# 01_USB_Interface.net
KiCad netlist of a schematic drawn in Altium Designer
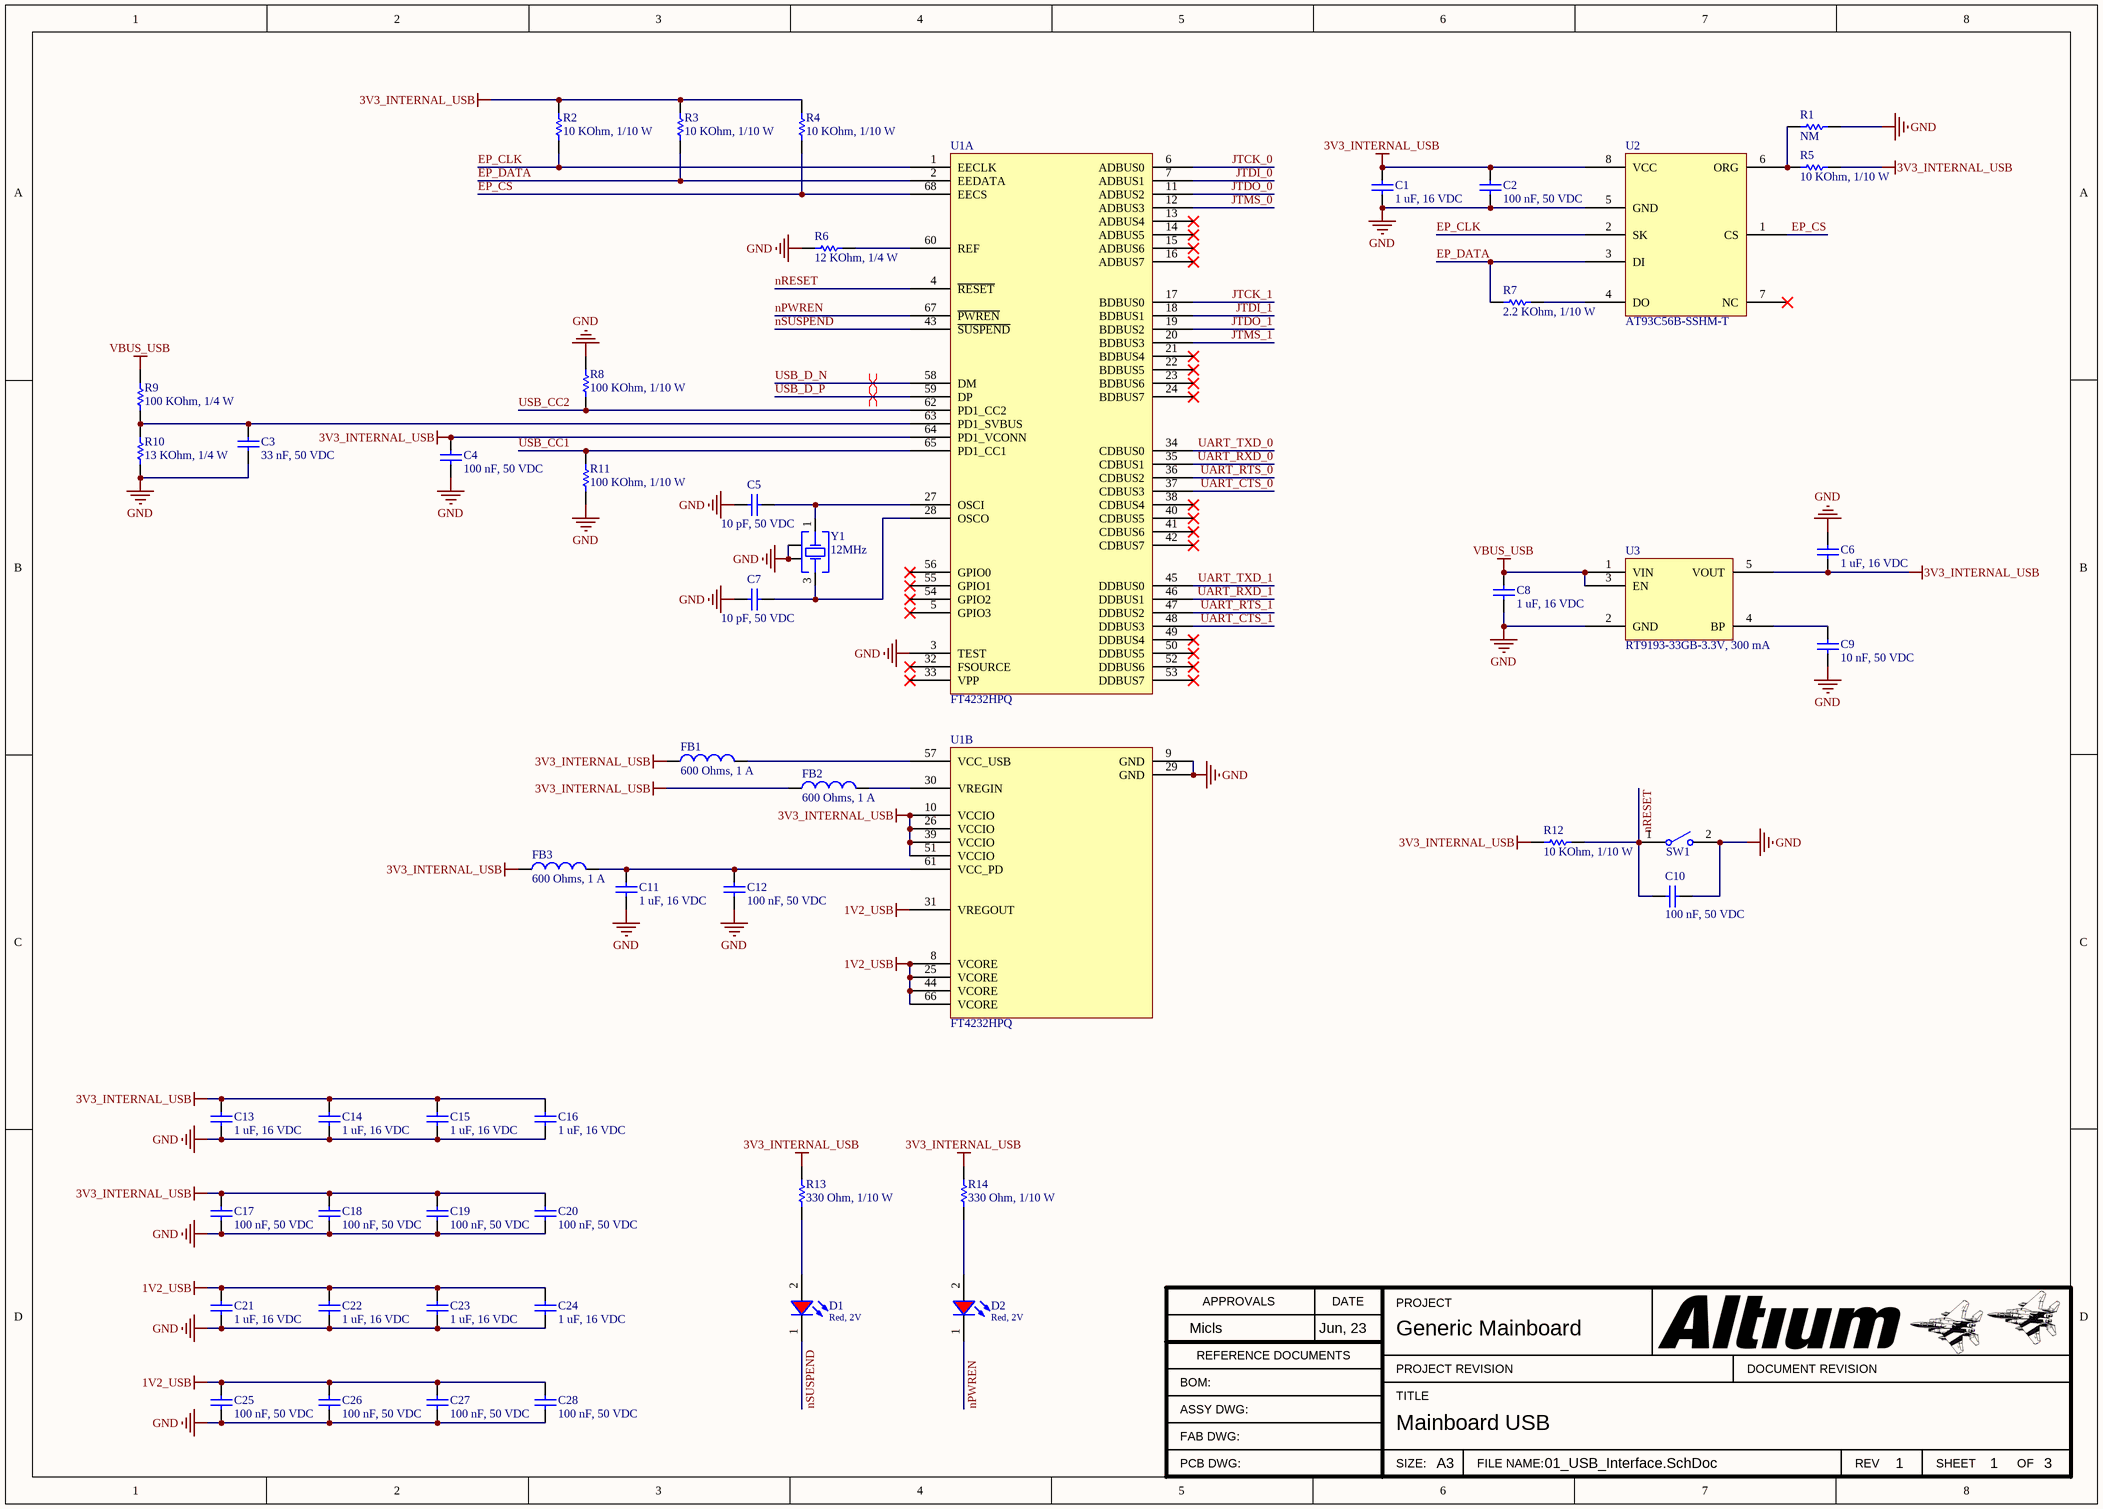
[diagram p0: 01_USB_Interface.SchDoc]

(export (version "E")
  (design (tool "Eeschema 10.0.6"))
  (components
    (comp (ref "C1")
      (value "1 uF, 16 VDC")
      (footprint "CAP_0603")
      (description "CAP, size 0603, 1 uF, 16 VDC")
      (fields (field (name "TOLERANCE") "+/-10%") (field (name "MANUFACTURER") "Samsung Electro-Mechanics"))
      (libsource (lib "Altium_Ceramic_Cap") (part "0106031051016"))
    )
    (comp (ref "C2")
      (value "100 nF, 50 VDC")
      (footprint "CAP_0603")
      (description "CAP, size 0603, 100 nF, 50 VDC")
      (fields (field (name "TOLERANCE") "+/-10%") (field (name "MANUFACTURER") "TDK"))
      (libsource (lib "Altium_Ceramic_Cap") (part "0106031041050"))
    )
    (comp (ref "C3")
      (value "33 nF, 50 VDC")
      (footprint "CAP_0603")
      (description "CAP, size 0603, 33 nF, 50 VDC")
      (fields (field (name "TOLERANCE") "+/-10%") (field (name "MANUFACTURER") "TDK"))
      (libsource (lib "Altium_Ceramic_Cap") (part "0106033331050"))
    )
    (comp (ref "C4")
      (value "100 nF, 50 VDC")
      (footprint "CAP_0603")
      (description "CAP, size 0603, 100 nF, 50 VDC")
      (fields (field (name "TOLERANCE") "+/-10%") (field (name "MANUFACTURER") "TDK"))
      (libsource (lib "Altium_Ceramic_Cap") (part "0106031041050"))
    )
    (comp (ref "C5")
      (value "10 pF, 50 VDC")
      (footprint "CAP_0603")
      (description "CAP, size 0603, 10 pF, 50 VDC")
      (fields (field (name "TOLERANCE") "+/-5%") (field (name "MANUFACTURER") "TDK"))
      (libsource (lib "Altium_Ceramic_Cap") (part "0106031000550"))
    )
    (comp (ref "C6")
      (value "1 uF, 16 VDC")
      (footprint "CAP_0603")
      (description "CAP, size 0603, 1 uF, 16 VDC")
      (fields (field (name "TOLERANCE") "+/-10%") (field (name "MANUFACTURER") "Samsung Electro-Mechanics"))
      (libsource (lib "Altium_Ceramic_Cap") (part "0106031051016"))
    )
    (comp (ref "C7")
      (value "10 pF, 50 VDC")
      (footprint "CAP_0603")
      (description "CAP, size 0603, 10 pF, 50 VDC")
      (fields (field (name "TOLERANCE") "+/-5%") (field (name "MANUFACTURER") "TDK"))
      (libsource (lib "Altium_Ceramic_Cap") (part "0106031000550"))
    )
    (comp (ref "C8")
      (value "1 uF, 16 VDC")
      (footprint "CAP_0603")
      (description "CAP, size 0603, 1 uF, 16 VDC")
      (fields (field (name "TOLERANCE") "+/-10%") (field (name "MANUFACTURER") "Samsung Electro-Mechanics"))
      (libsource (lib "Altium_Ceramic_Cap") (part "0106031051016"))
    )
    (comp (ref "C9")
      (value "10 nF, 50 VDC")
      (footprint "CAP_0603")
      (description "CAP, size 0603, 10 nF, 50 VDC")
      (fields (field (name "TOLERANCE") "+/-5%") (field (name "MANUFACTURER") "TDK"))
      (libsource (lib "Altium_Ceramic_Cap") (part "0106031030550"))
    )
    (comp (ref "C10")
      (value "100 nF, 50 VDC")
      (footprint "CAP_0603")
      (description "CAP, size 0603, 100 nF, 50 VDC")
      (fields (field (name "TOLERANCE") "+/-10%") (field (name "MANUFACTURER") "TDK"))
      (libsource (lib "Altium_Ceramic_Cap") (part "0106031041050"))
    )
    (comp (ref "C11")
      (value "1 uF, 16 VDC")
      (footprint "CAP_0603")
      (description "CAP, size 0603, 1 uF, 16 VDC")
      (fields (field (name "TOLERANCE") "+/-10%") (field (name "MANUFACTURER") "Samsung Electro-Mechanics"))
      (libsource (lib "Altium_Ceramic_Cap") (part "0106031051016"))
    )
    (comp (ref "C12")
      (value "100 nF, 50 VDC")
      (footprint "CAP_0603")
      (description "CAP, size 0603, 100 nF, 50 VDC")
      (fields (field (name "TOLERANCE") "+/-10%") (field (name "MANUFACTURER") "TDK"))
      (libsource (lib "Altium_Ceramic_Cap") (part "0106031041050"))
    )
    (comp (ref "C13")
      (value "1 uF, 16 VDC")
      (footprint "CAP_0603")
      (description "CAP, size 0603, 1 uF, 16 VDC")
      (fields (field (name "TOLERANCE") "+/-10%") (field (name "MANUFACTURER") "Samsung Electro-Mechanics"))
      (libsource (lib "Altium_Ceramic_Cap") (part "0106031051016"))
    )
    (comp (ref "C14")
      (value "1 uF, 16 VDC")
      (footprint "CAP_0603")
      (description "CAP, size 0603, 1 uF, 16 VDC")
      (fields (field (name "TOLERANCE") "+/-10%") (field (name "MANUFACTURER") "Samsung Electro-Mechanics"))
      (libsource (lib "Altium_Ceramic_Cap") (part "0106031051016"))
    )
    (comp (ref "C15")
      (value "1 uF, 16 VDC")
      (footprint "CAP_0603")
      (description "CAP, size 0603, 1 uF, 16 VDC")
      (fields (field (name "TOLERANCE") "+/-10%") (field (name "MANUFACTURER") "Samsung Electro-Mechanics"))
      (libsource (lib "Altium_Ceramic_Cap") (part "0106031051016"))
    )
    (comp (ref "C16")
      (value "1 uF, 16 VDC")
      (footprint "CAP_0603")
      (description "CAP, size 0603, 1 uF, 16 VDC")
      (fields (field (name "TOLERANCE") "+/-10%") (field (name "MANUFACTURER") "Samsung Electro-Mechanics"))
      (libsource (lib "Altium_Ceramic_Cap") (part "0106031051016"))
    )
    (comp (ref "C17")
      (value "100 nF, 50 VDC")
      (footprint "CAP_0603")
      (description "CAP, size 0603, 100 nF, 50 VDC")
      (fields (field (name "TOLERANCE") "+/-10%") (field (name "MANUFACTURER") "TDK"))
      (libsource (lib "Altium_Ceramic_Cap") (part "0106031041050"))
    )
    (comp (ref "C18")
      (value "100 nF, 50 VDC")
      (footprint "CAP_0603")
      (description "CAP, size 0603, 100 nF, 50 VDC")
      (fields (field (name "TOLERANCE") "+/-10%") (field (name "MANUFACTURER") "TDK"))
      (libsource (lib "Altium_Ceramic_Cap") (part "0106031041050"))
    )
    (comp (ref "C19")
      (value "100 nF, 50 VDC")
      (footprint "CAP_0603")
      (description "CAP, size 0603, 100 nF, 50 VDC")
      (fields (field (name "TOLERANCE") "+/-10%") (field (name "MANUFACTURER") "TDK"))
      (libsource (lib "Altium_Ceramic_Cap") (part "0106031041050"))
    )
    (comp (ref "C20")
      (value "100 nF, 50 VDC")
      (footprint "CAP_0603")
      (description "CAP, size 0603, 100 nF, 50 VDC")
      (fields (field (name "TOLERANCE") "+/-10%") (field (name "MANUFACTURER") "TDK"))
      (libsource (lib "Altium_Ceramic_Cap") (part "0106031041050"))
    )
    (comp (ref "C21")
      (value "1 uF, 16 VDC")
      (footprint "CAP_0603")
      (description "CAP, size 0603, 1 uF, 16 VDC")
      (fields (field (name "TOLERANCE") "+/-10%") (field (name "MANUFACTURER") "Samsung Electro-Mechanics"))
      (libsource (lib "Altium_Ceramic_Cap") (part "0106031051016"))
    )
    (comp (ref "C22")
      (value "1 uF, 16 VDC")
      (footprint "CAP_0603")
      (description "CAP, size 0603, 1 uF, 16 VDC")
      (fields (field (name "TOLERANCE") "+/-10%") (field (name "MANUFACTURER") "Samsung Electro-Mechanics"))
      (libsource (lib "Altium_Ceramic_Cap") (part "0106031051016"))
    )
    (comp (ref "C23")
      (value "1 uF, 16 VDC")
      (footprint "CAP_0603")
      (description "CAP, size 0603, 1 uF, 16 VDC")
      (fields (field (name "TOLERANCE") "+/-10%") (field (name "MANUFACTURER") "Samsung Electro-Mechanics"))
      (libsource (lib "Altium_Ceramic_Cap") (part "0106031051016"))
    )
    (comp (ref "C24")
      (value "1 uF, 16 VDC")
      (footprint "CAP_0603")
      (description "CAP, size 0603, 1 uF, 16 VDC")
      (fields (field (name "TOLERANCE") "+/-10%") (field (name "MANUFACTURER") "Samsung Electro-Mechanics"))
      (libsource (lib "Altium_Ceramic_Cap") (part "0106031051016"))
    )
    (comp (ref "C25")
      (value "100 nF, 50 VDC")
      (footprint "CAP_0603")
      (description "CAP, size 0603, 100 nF, 50 VDC")
      (fields (field (name "TOLERANCE") "+/-10%") (field (name "MANUFACTURER") "TDK"))
      (libsource (lib "Altium_Ceramic_Cap") (part "0106031041050"))
    )
    (comp (ref "C26")
      (value "100 nF, 50 VDC")
      (footprint "CAP_0603")
      (description "CAP, size 0603, 100 nF, 50 VDC")
      (fields (field (name "TOLERANCE") "+/-10%") (field (name "MANUFACTURER") "TDK"))
      (libsource (lib "Altium_Ceramic_Cap") (part "0106031041050"))
    )
    (comp (ref "C27")
      (value "100 nF, 50 VDC")
      (footprint "CAP_0603")
      (description "CAP, size 0603, 100 nF, 50 VDC")
      (fields (field (name "TOLERANCE") "+/-10%") (field (name "MANUFACTURER") "TDK"))
      (libsource (lib "Altium_Ceramic_Cap") (part "0106031041050"))
    )
    (comp (ref "C28")
      (value "100 nF, 50 VDC")
      (footprint "CAP_0603")
      (description "CAP, size 0603, 100 nF, 50 VDC")
      (fields (field (name "TOLERANCE") "+/-10%") (field (name "MANUFACTURER") "TDK"))
      (libsource (lib "Altium_Ceramic_Cap") (part "0106031041050"))
    )
    (comp (ref "D1")
      (value "Red, 2V")
      (footprint "WL-SMCW_0603_H=0.7mm")
      (description "WL-SMCW SMT Mono-color Chip LED Blur, size 0603, Red, 2V, 140deg")
      (fields
        (field (name "MANUFACTURER") "ROHM Semiconductor")
        (field (name "MANUFACTURER PART NUMBER") "CSL1901VW1")
      )
      (libsource (lib "Altium_LED") (part "160603RedBlur"))
    )
    (comp (ref "D2")
      (value "Red, 2V")
      (footprint "WL-SMCW_0603_H=0.7mm")
      (description "WL-SMCW SMT Mono-color Chip LED Blur, size 0603, Red, 2V, 140deg")
      (fields
        (field (name "MANUFACTURER") "ROHM Semiconductor")
        (field (name "MANUFACTURER PART NUMBER") "CSL1901VW1")
      )
      (libsource (lib "Altium_LED") (part "160603RedBlur"))
    )
    (comp (ref "FB1")
      (value "600 Ohms, 1 A")
      (footprint "FER_0603")
      (description "Ferrite, 0603, 600 Ohms, 1 A")
      (fields (field (name "TOLERANCE") "+/-25%") (field (name "MANUFACTURER") "Wurth Elektronik"))
      (libsource (lib "Altium_Ferrite_Bead") (part "03060360110225"))
    )
    (comp (ref "FB2")
      (value "600 Ohms, 1 A")
      (footprint "FER_0603")
      (description "Ferrite, 0603, 600 Ohms, 1 A")
      (fields (field (name "TOLERANCE") "+/-25%") (field (name "MANUFACTURER") "Wurth Elektronik"))
      (libsource (lib "Altium_Ferrite_Bead") (part "03060360110225"))
    )
    (comp (ref "FB3")
      (value "600 Ohms, 1 A")
      (footprint "FER_0603")
      (description "Ferrite, 0603, 600 Ohms, 1 A")
      (fields (field (name "TOLERANCE") "+/-25%") (field (name "MANUFACTURER") "Wurth Elektronik"))
      (libsource (lib "Altium_Ferrite_Bead") (part "03060360110225"))
    )
    (comp (ref "R1")
      (value "NM")
      (footprint "RES_0603")
      (description "RES, size 0603, NM, N/A")
      (libsource (lib "Altium_Resistor") (part "000603_NM"))
    )
    (comp (ref "R2")
      (value "10 KOhm, 1/10 W")
      (footprint "RES_0603")
      (description "RES, size 0603, 10 KOhm, 1/10 W, 1%")
      (fields (field (name "TOLERANCE") "+/-1%") (field (name "MANUFACTURER") "YAGEO"))
      (libsource (lib "Altium_Resistor") (part "0006031031"))
    )
    (comp (ref "R3")
      (value "10 KOhm, 1/10 W")
      (footprint "RES_0603")
      (description "RES, size 0603, 10 KOhm, 1/10 W, 1%")
      (fields (field (name "TOLERANCE") "+/-1%") (field (name "MANUFACTURER") "YAGEO"))
      (libsource (lib "Altium_Resistor") (part "0006031031"))
    )
    (comp (ref "R4")
      (value "10 KOhm, 1/10 W")
      (footprint "RES_0603")
      (description "RES, size 0603, 10 KOhm, 1/10 W, 1%")
      (fields (field (name "TOLERANCE") "+/-1%") (field (name "MANUFACTURER") "YAGEO"))
      (libsource (lib "Altium_Resistor") (part "0006031031"))
    )
    (comp (ref "R5")
      (value "10 KOhm, 1/10 W")
      (footprint "RES_0603")
      (description "RES, size 0603, 10 KOhm, 1/10 W, 1%")
      (fields (field (name "TOLERANCE") "+/-1%") (field (name "MANUFACTURER") "YAGEO"))
      (libsource (lib "Altium_Resistor") (part "0006031031"))
    )
    (comp (ref "R6")
      (value "12 KOhm, 1/4 W")
      (footprint "RES_0603")
      (description "RES, size 0603, 12 KOhm, 1/4 W")
      (fields (field (name "TOLERANCE") "+/-1%") (field (name "MANUFACTURER") "OEM"))
      (libsource (lib "Altium_Resistor") (part "0006031231"))
    )
    (comp (ref "R7")
      (value "2.2 KOhm, 1/10 W")
      (footprint "RES_0603")
      (description "RES, size 0603, 2.2  KOhm, 1/10 W, 1%")
      (fields (field (name "TOLERANCE") "+/-1%") (field (name "MANUFACTURER") "OEM"))
      (libsource (lib "Altium_Resistor") (part "0006032221"))
    )
    (comp (ref "R8")
      (value "100 KOhm, 1/10 W")
      (footprint "RES_0603")
      (description "RES, size 0603, 100 KOhm, 1/10 W, 1%")
      (fields (field (name "TOLERANCE") "+/-1%") (field (name "MANUFACTURER") "OEM"))
      (libsource (lib "Altium_Resistor") (part "0006031041"))
    )
    (comp (ref "R9")
      (value "100 KOhm, 1/4 W")
      (footprint "RES_0603")
      (description "RES, size 0603, 100 KOhm, 1/4 W")
      (fields (field (name "TOLERANCE") "+/-1%") (field (name "MANUFACTURER") "OEM"))
      (libsource (lib "Altium_Resistor") (part "0006031041"))
    )
    (comp (ref "R10")
      (value "13 KOhm, 1/4 W")
      (footprint "RES_0603")
      (description "RES, size 0603, 13 KOhm, 1/4 W")
      (fields (field (name "TOLERANCE") "+/-1%") (field (name "MANUFACTURER") "OEM"))
      (libsource (lib "Altium_Resistor") (part "0006031331"))
    )
    (comp (ref "R11")
      (value "100 KOhm, 1/10 W")
      (footprint "RES_0603")
      (description "RES, size 0603, 100 KOhm, 1/10 W, 1%")
      (fields (field (name "TOLERANCE") "+/-1%") (field (name "MANUFACTURER") "OEM"))
      (libsource (lib "Altium_Resistor") (part "0006031041"))
    )
    (comp (ref "R12")
      (value "10 KOhm, 1/10 W")
      (footprint "RES_0603")
      (description "RES, size 0603, 10 KOhm, 1/10 W, 1%")
      (fields (field (name "TOLERANCE") "+/-1%") (field (name "MANUFACTURER") "YAGEO"))
      (libsource (lib "Altium_Resistor") (part "0006031031"))
    )
    (comp (ref "R13")
      (value "330 Ohm, 1/10 W")
      (footprint "RES_0603")
      (description "RES, size 0603, 330 Ohm, 1/10 W")
      (fields (field (name "TOLERANCE") "+/-1%") (field (name "MANUFACTURER") "OEM"))
      (libsource (lib "Altium_Resistor") (part "0006033311"))
    )
    (comp (ref "R14")
      (value "330 Ohm, 1/10 W")
      (footprint "RES_0603")
      (description "RES, size 0603, 330 Ohm, 1/10 W")
      (fields (field (name "TOLERANCE") "+/-1%") (field (name "MANUFACTURER") "OEM"))
      (libsource (lib "Altium_Resistor") (part "0006033311"))
    )
    (comp (ref "SW1")
      (value "TS-1101-C-W")
      (footprint "TS-1101-C-W")
      (description "Tact Switch, L6 x W3.8 x H2.5mm, 260g, SPST-NO, 12V, 50mA")
      (fields
        (field (name "MANUFACTURER") "Wurth Elektronik")
        (field (name "LCSC PART #") "XKB Connectivity")
      )
      (libsource (lib "Altium_Button") (part "TS-1101-C-W"))
    )
    (comp (ref "U1")
      (value "FT4232HPQ")
      (footprint "FT4232HPQ")
      (description "USB Interface IC USB Bridge Type-C 3.0 32-Bit 8kB 48kB")
      (fields (field (name "MANUFACTURER") "FTDI"))
      (libsource (lib "USB_Interface") (part "FT4232HPQ"))
    )
    (comp (ref "U2")
      (value "AT93C56B-SSHM-T")
      (footprint "AT93C56B")
      (description "EEPROM 2K (256x8/128x16) 3-WIRE, NiPdAu, 1.7V")
      (fields (field (name "MANUFACTURER") "Microchip") (field (name "LCSC PART #") "C111441"))
      (libsource (lib "EEPROM") (part "AT93C56B-SSHM-T"))
    )
    (comp (ref "U3")
      (value "RT9193-33GB-3.3V, 300 mA")
      (footprint "RT9193-xxGB")
      (description "LDO Voltage Regulators 300mA, Ultra-Low Noise, Ultra-Fast CMOS LDO Regulator, SOT-23-5,  3.3 V")
      (fields (field (name "MANUFACTURER") "Richtek") (field (name "MANUFACTURER PART NUMBER") "RT9193-33GB"))
      (libsource (lib "Altium_Power_Supply_IC") (part "RT9193-33GB"))
    )
    (comp (ref "Y1")
      (value "12MHz")
      (footprint "WE-XTAL_CFPX-180")
      (description "WE-XTAL Quartz Crystal, SMT, CFPX-180, 12MHz, +/-30ppm")
      (fields
        (field (name "MANUFACTURER PART NUMBER") "NX3225SA-12MHZ-STD-CSR-6")
        (field (name "MANUFACTURER") "NDK")
      )
      (libsource (lib "Altium_XTAL") (part "073525126010"))
    )
  )
  (nets
    (net (code "1") (name "/EP_CLK") (class "Default")
      (node (ref "R2") (pin "1") (pinfunction "1_1") (pintype "passive"))
      (node (ref "U1") (pin "1") (pinfunction "EECLK_1") (pintype "passive"))
      (node (ref "U2") (pin "2") (pinfunction "SK_2") (pintype "passive"))
    )
    (net (code "2") (name "/EP_CS") (class "Default")
      (node (ref "R4") (pin "1") (pinfunction "1_1") (pintype "passive"))
      (node (ref "U1") (pin "68") (pinfunction "EECS_68") (pintype "passive"))
      (node (ref "U2") (pin "1") (pinfunction "CS_1") (pintype "passive"))
    )
    (net (code "3") (name "/EP_DATA") (class "Default")
      (node (ref "R3") (pin "1") (pinfunction "1_1") (pintype "passive"))
      (node (ref "R7") (pin "1") (pinfunction "1_1") (pintype "passive"))
      (node (ref "U1") (pin "2") (pinfunction "EEDATA_2") (pintype "passive"))
      (node (ref "U2") (pin "3") (pinfunction "DI_3") (pintype "passive"))
    )
    (net (code "4") (name "/JTCK_0") (class "Default")
      (node (ref "U1") (pin "6") (pinfunction "ADBUS0_6") (pintype "passive"))
    )
    (net (code "5") (name "/JTCK_1") (class "Default")
      (node (ref "U1") (pin "17") (pinfunction "BDBUS0_17") (pintype "passive"))
    )
    (net (code "6") (name "/JTDI_0") (class "Default")
      (node (ref "U1") (pin "7") (pinfunction "ADBUS1_7") (pintype "passive"))
    )
    (net (code "7") (name "/JTDI_1") (class "Default")
      (node (ref "U1") (pin "18") (pinfunction "BDBUS1_18") (pintype "passive"))
    )
    (net (code "8") (name "/JTDO_0") (class "Default")
      (node (ref "U1") (pin "11") (pinfunction "ADBUS2_11") (pintype "passive"))
    )
    (net (code "9") (name "/JTDO_1") (class "Default")
      (node (ref "U1") (pin "19") (pinfunction "BDBUS2_19") (pintype "passive"))
    )
    (net (code "10") (name "/JTMS_0") (class "Default")
      (node (ref "U1") (pin "12") (pinfunction "ADBUS3_12") (pintype "passive"))
    )
    (net (code "11") (name "/JTMS_1") (class "Default")
      (node (ref "U1") (pin "20") (pinfunction "BDBUS3_20") (pintype "passive"))
    )
    (net (code "12") (name "/UART_CTS_0") (class "Default")
      (node (ref "U1") (pin "37") (pinfunction "CDBUS3_37") (pintype "passive"))
    )
    (net (code "13") (name "/UART_CTS_1") (class "Default")
      (node (ref "U1") (pin "48") (pinfunction "DDBUS3_48") (pintype "passive"))
    )
    (net (code "14") (name "/UART_RTS_0") (class "Default")
      (node (ref "U1") (pin "36") (pinfunction "CDBUS2_36") (pintype "passive"))
    )
    (net (code "15") (name "/UART_RTS_1") (class "Default")
      (node (ref "U1") (pin "47") (pinfunction "DDBUS2_47") (pintype "passive"))
    )
    (net (code "16") (name "/UART_RXD_0") (class "Default")
      (node (ref "U1") (pin "35") (pinfunction "CDBUS1_35") (pintype "passive"))
    )
    (net (code "17") (name "/UART_RXD_1") (class "Default")
      (node (ref "U1") (pin "46") (pinfunction "DDBUS1_46") (pintype "passive"))
    )
    (net (code "18") (name "/UART_TXD_0") (class "Default")
      (node (ref "U1") (pin "34") (pinfunction "CDBUS0_34") (pintype "passive"))
    )
    (net (code "19") (name "/UART_TXD_1") (class "Default")
      (node (ref "U1") (pin "45") (pinfunction "DDBUS0_45") (pintype "passive"))
    )
    (net (code "20") (name "/USB_CC1") (class "Default")
      (node (ref "R11") (pin "2") (pinfunction "2_2") (pintype "passive"))
      (node (ref "U1") (pin "65") (pinfunction "PD1_CC1_65") (pintype "passive"))
    )
    (net (code "21") (name "/USB_CC2") (class "Default")
      (node (ref "R8") (pin "2") (pinfunction "2_2") (pintype "passive"))
      (node (ref "U1") (pin "62") (pinfunction "PD1_CC2_62") (pintype "passive"))
    )
    (net (code "22") (name "/USB_D_N") (class "Default")
      (node (ref "U1") (pin "58") (pinfunction "DM_58") (pintype "passive"))
    )
    (net (code "23") (name "/USB_D_P") (class "Default")
      (node (ref "U1") (pin "59") (pinfunction "DP_59") (pintype "passive"))
    )
    (net (code "24") (name "/nPWREN") (class "Default")
      (node (ref "D2") (pin "1") (pinfunction "K_1") (pintype "passive"))
      (node (ref "U1") (pin "67") (pinfunction "~{PWREN}_67") (pintype "passive"))
    )
    (net (code "25") (name "/nRESET") (class "Default")
      (node (ref "C10") (pin "2") (pinfunction "2_2") (pintype "passive"))
      (node (ref "R12") (pin "1") (pinfunction "1_1") (pintype "passive"))
      (node (ref "SW1") (pin "1") (pinfunction "1_1") (pintype "passive"))
      (node (ref "U1") (pin "4") (pinfunction "~{RESET}_4") (pintype "passive"))
    )
    (net (code "26") (name "/nSUSPEND") (class "Default")
      (node (ref "D1") (pin "1") (pinfunction "K_1") (pintype "passive"))
      (node (ref "U1") (pin "43") (pinfunction "~{SUSPEND}_43") (pintype "passive"))
    )
    (net (code "27") (name "1V2_USB") (class "Default")
      (node (ref "C21") (pin "2") (pinfunction "2_2") (pintype "passive"))
      (node (ref "C22") (pin "2") (pinfunction "2_2") (pintype "passive"))
      (node (ref "C23") (pin "2") (pinfunction "2_2") (pintype "passive"))
      (node (ref "C24") (pin "2") (pinfunction "2_2") (pintype "passive"))
      (node (ref "C25") (pin "2") (pinfunction "2_2") (pintype "passive"))
      (node (ref "C26") (pin "2") (pinfunction "2_2") (pintype "passive"))
      (node (ref "C27") (pin "2") (pinfunction "2_2") (pintype "passive"))
      (node (ref "C28") (pin "2") (pinfunction "2_2") (pintype "passive"))
      (node (ref "U1") (pin "25") (pinfunction "VCORE_25") (pintype "passive"))
      (node (ref "U1") (pin "31") (pinfunction "VREGOUT_31") (pintype "passive"))
      (node (ref "U1") (pin "44") (pinfunction "VCORE_44") (pintype "passive"))
      (node (ref "U1") (pin "66") (pinfunction "VCORE_66") (pintype "passive"))
      (node (ref "U1") (pin "8") (pinfunction "VCORE_8") (pintype "passive"))
    )
    (net (code "28") (name "3V3_INTERNAL_USB") (class "Default")
      (node (ref "C1") (pin "2") (pinfunction "2_2") (pintype "passive"))
      (node (ref "C13") (pin "2") (pinfunction "2_2") (pintype "passive"))
      (node (ref "C14") (pin "2") (pinfunction "2_2") (pintype "passive"))
      (node (ref "C15") (pin "2") (pinfunction "2_2") (pintype "passive"))
      (node (ref "C16") (pin "2") (pinfunction "2_2") (pintype "passive"))
      (node (ref "C17") (pin "2") (pinfunction "2_2") (pintype "passive"))
      (node (ref "C18") (pin "2") (pinfunction "2_2") (pintype "passive"))
      (node (ref "C19") (pin "2") (pinfunction "2_2") (pintype "passive"))
      (node (ref "C2") (pin "2") (pinfunction "2_2") (pintype "passive"))
      (node (ref "C20") (pin "2") (pinfunction "2_2") (pintype "passive"))
      (node (ref "C4") (pin "2") (pinfunction "2_2") (pintype "passive"))
      (node (ref "C6") (pin "2") (pinfunction "2_2") (pintype "passive"))
      (node (ref "FB1") (pin "1") (pinfunction "1_1") (pintype "passive"))
      (node (ref "FB2") (pin "1") (pinfunction "1_1") (pintype "passive"))
      (node (ref "FB3") (pin "1") (pinfunction "1_1") (pintype "passive"))
      (node (ref "R12") (pin "2") (pinfunction "2_2") (pintype "passive"))
      (node (ref "R13") (pin "2") (pinfunction "2_2") (pintype "passive"))
      (node (ref "R14") (pin "2") (pinfunction "2_2") (pintype "passive"))
      (node (ref "R2") (pin "2") (pinfunction "2_2") (pintype "passive"))
      (node (ref "R3") (pin "2") (pinfunction "2_2") (pintype "passive"))
      (node (ref "R4") (pin "2") (pinfunction "2_2") (pintype "passive"))
      (node (ref "R5") (pin "2") (pinfunction "2_2") (pintype "passive"))
      (node (ref "U1") (pin "10") (pinfunction "VCCIO_10") (pintype "passive"))
      (node (ref "U1") (pin "26") (pinfunction "VCCIO_26") (pintype "passive"))
      (node (ref "U1") (pin "39") (pinfunction "VCCIO_39") (pintype "passive"))
      (node (ref "U1") (pin "51") (pinfunction "VCCIO_51") (pintype "passive"))
      (node (ref "U1") (pin "64") (pinfunction "PD1_VCONN_64") (pintype "passive"))
      (node (ref "U2") (pin "8") (pinfunction "VCC_8") (pintype "passive"))
      (node (ref "U3") (pin "5") (pinfunction "VOUT_5") (pintype "power_in"))
    )
    (net (code "29") (name "GND") (class "Default")
      (node (ref "C1") (pin "1") (pinfunction "1_1") (pintype "passive"))
      (node (ref "C10") (pin "1") (pinfunction "1_1") (pintype "passive"))
      (node (ref "C11") (pin "1") (pinfunction "1_1") (pintype "passive"))
      (node (ref "C12") (pin "1") (pinfunction "1_1") (pintype "passive"))
      (node (ref "C13") (pin "1") (pinfunction "1_1") (pintype "passive"))
      (node (ref "C14") (pin "1") (pinfunction "1_1") (pintype "passive"))
      (node (ref "C15") (pin "1") (pinfunction "1_1") (pintype "passive"))
      (node (ref "C16") (pin "1") (pinfunction "1_1") (pintype "passive"))
      (node (ref "C17") (pin "1") (pinfunction "1_1") (pintype "passive"))
      (node (ref "C18") (pin "1") (pinfunction "1_1") (pintype "passive"))
      (node (ref "C19") (pin "1") (pinfunction "1_1") (pintype "passive"))
      (node (ref "C2") (pin "1") (pinfunction "1_1") (pintype "passive"))
      (node (ref "C20") (pin "1") (pinfunction "1_1") (pintype "passive"))
      (node (ref "C21") (pin "1") (pinfunction "1_1") (pintype "passive"))
      (node (ref "C22") (pin "1") (pinfunction "1_1") (pintype "passive"))
      (node (ref "C23") (pin "1") (pinfunction "1_1") (pintype "passive"))
      (node (ref "C24") (pin "1") (pinfunction "1_1") (pintype "passive"))
      (node (ref "C25") (pin "1") (pinfunction "1_1") (pintype "passive"))
      (node (ref "C26") (pin "1") (pinfunction "1_1") (pintype "passive"))
      (node (ref "C27") (pin "1") (pinfunction "1_1") (pintype "passive"))
      (node (ref "C28") (pin "1") (pinfunction "1_1") (pintype "passive"))
      (node (ref "C3") (pin "1") (pinfunction "1_1") (pintype "passive"))
      (node (ref "C4") (pin "1") (pinfunction "1_1") (pintype "passive"))
      (node (ref "C5") (pin "1") (pinfunction "1_1") (pintype "passive"))
      (node (ref "C6") (pin "1") (pinfunction "1_1") (pintype "passive"))
      (node (ref "C7") (pin "1") (pinfunction "1_1") (pintype "passive"))
      (node (ref "C8") (pin "1") (pinfunction "1_1") (pintype "passive"))
      (node (ref "C9") (pin "1") (pinfunction "1_1") (pintype "passive"))
      (node (ref "R1") (pin "1") (pinfunction "1_1") (pintype "passive"))
      (node (ref "R10") (pin "1") (pinfunction "1_1") (pintype "passive"))
      (node (ref "R11") (pin "1") (pinfunction "1_1") (pintype "passive"))
      (node (ref "R6") (pin "1") (pinfunction "1_1") (pintype "passive"))
      (node (ref "R8") (pin "1") (pinfunction "1_1") (pintype "passive"))
      (node (ref "SW1") (pin "2") (pinfunction "2_2") (pintype "passive"))
      (node (ref "U1") (pin "29") (pinfunction "GND_29") (pintype "passive"))
      (node (ref "U1") (pin "3") (pinfunction "TEST_3") (pintype "passive"))
      (node (ref "U1") (pin "9") (pinfunction "GND_9") (pintype "passive"))
      (node (ref "U2") (pin "5") (pinfunction "GND_5") (pintype "passive"))
      (node (ref "U3") (pin "2") (pinfunction "GND_2") (pintype "power_in"))
      (node (ref "Y1") (pin "2") (pinfunction "GND_2") (pintype "passive"))
      (node (ref "Y1") (pin "4") (pinfunction "GND_4") (pintype "passive"))
    )
    (net (code "30") (name "Net-(D1-A)") (class "Default")
      (node (ref "D1") (pin "2") (pinfunction "A_2") (pintype "passive"))
      (node (ref "R13") (pin "1") (pinfunction "1_1") (pintype "passive"))
    )
    (net (code "31") (name "Net-(D2-A)") (class "Default")
      (node (ref "D2") (pin "2") (pinfunction "A_2") (pintype "passive"))
      (node (ref "R14") (pin "1") (pinfunction "1_1") (pintype "passive"))
    )
    (net (code "32") (name "Net-(U1A-OSCI)") (class "Default")
      (node (ref "C5") (pin "2") (pinfunction "2_2") (pintype "passive"))
      (node (ref "U1") (pin "27") (pinfunction "OSCI_27") (pintype "passive"))
      (node (ref "Y1") (pin "1") (pinfunction "Crystal_1") (pintype "passive"))
    )
    (net (code "33") (name "Net-(U1A-OSCO)") (class "Default")
      (node (ref "C7") (pin "2") (pinfunction "2_2") (pintype "passive"))
      (node (ref "U1") (pin "28") (pinfunction "OSCO_28") (pintype "passive"))
      (node (ref "Y1") (pin "3") (pinfunction "Crystal_3") (pintype "passive"))
    )
    (net (code "34") (name "Net-(U1A-PD1_SVBUS)") (class "Default")
      (node (ref "C3") (pin "2") (pinfunction "2_2") (pintype "passive"))
      (node (ref "R10") (pin "2") (pinfunction "2_2") (pintype "passive"))
      (node (ref "R9") (pin "1") (pinfunction "1_1") (pintype "passive"))
      (node (ref "U1") (pin "63") (pinfunction "PD1_SVBUS_63") (pintype "passive"))
    )
    (net (code "35") (name "Net-(U1A-REF)") (class "Default")
      (node (ref "R6") (pin "2") (pinfunction "2_2") (pintype "passive"))
      (node (ref "U1") (pin "60") (pinfunction "REF_60") (pintype "passive"))
    )
    (net (code "36") (name "Net-(U1B-VCC_PD)") (class "Default")
      (node (ref "C11") (pin "2") (pinfunction "2_2") (pintype "passive"))
      (node (ref "C12") (pin "2") (pinfunction "2_2") (pintype "passive"))
      (node (ref "FB3") (pin "2") (pinfunction "2_2") (pintype "passive"))
      (node (ref "U1") (pin "61") (pinfunction "VCC_PD_61") (pintype "passive"))
    )
    (net (code "37") (name "Net-(U1B-VCC_USB)") (class "Default")
      (node (ref "FB1") (pin "2") (pinfunction "2_2") (pintype "passive"))
      (node (ref "U1") (pin "57") (pinfunction "VCC_USB_57") (pintype "passive"))
    )
    (net (code "38") (name "Net-(U1B-VREGIN)") (class "Default")
      (node (ref "FB2") (pin "2") (pinfunction "2_2") (pintype "passive"))
      (node (ref "U1") (pin "30") (pinfunction "VREGIN_30") (pintype "passive"))
    )
    (net (code "39") (name "Net-(U2-DO)") (class "Default")
      (node (ref "R7") (pin "2") (pinfunction "2_2") (pintype "passive"))
      (node (ref "U2") (pin "4") (pinfunction "DO_4") (pintype "passive"))
    )
    (net (code "40") (name "Net-(U2-ORG)") (class "Default")
      (node (ref "R1") (pin "2") (pinfunction "2_2") (pintype "passive"))
      (node (ref "R5") (pin "1") (pinfunction "1_1") (pintype "passive"))
      (node (ref "U2") (pin "6") (pinfunction "ORG_6") (pintype "passive"))
    )
    (net (code "41") (name "Net-(U3-BP)") (class "Default")
      (node (ref "C9") (pin "2") (pinfunction "2_2") (pintype "passive"))
      (node (ref "U3") (pin "4") (pinfunction "BP_4") (pintype "power_in"))
    )
    (net (code "42") (name "VBUS_USB") (class "Default")
      (node (ref "C8") (pin "2") (pinfunction "2_2") (pintype "passive"))
      (node (ref "R9") (pin "2") (pinfunction "2_2") (pintype "passive"))
      (node (ref "U3") (pin "1") (pinfunction "VIN_1") (pintype "power_in"))
      (node (ref "U3") (pin "3") (pinfunction "EN_3") (pintype "power_in"))
    )
    (net (code "43") (name "unconnected-(U1A-ADBUS4-Pad13)") (class "Default")
      (node (ref "U1") (pin "13") (pinfunction "ADBUS4_13") (pintype "passive+no_connect"))
    )
    (net (code "44") (name "unconnected-(U1A-ADBUS5-Pad14)") (class "Default")
      (node (ref "U1") (pin "14") (pinfunction "ADBUS5_14") (pintype "passive+no_connect"))
    )
    (net (code "45") (name "unconnected-(U1A-ADBUS6-Pad15)") (class "Default")
      (node (ref "U1") (pin "15") (pinfunction "ADBUS6_15") (pintype "passive+no_connect"))
    )
    (net (code "46") (name "unconnected-(U1A-ADBUS7-Pad16)") (class "Default")
      (node (ref "U1") (pin "16") (pinfunction "ADBUS7_16") (pintype "passive+no_connect"))
    )
    (net (code "47") (name "unconnected-(U1A-BDBUS4-Pad21)") (class "Default")
      (node (ref "U1") (pin "21") (pinfunction "BDBUS4_21") (pintype "passive+no_connect"))
    )
    (net (code "48") (name "unconnected-(U1A-BDBUS5-Pad22)") (class "Default")
      (node (ref "U1") (pin "22") (pinfunction "BDBUS5_22") (pintype "passive+no_connect"))
    )
    (net (code "49") (name "unconnected-(U1A-BDBUS6-Pad23)") (class "Default")
      (node (ref "U1") (pin "23") (pinfunction "BDBUS6_23") (pintype "passive+no_connect"))
    )
    (net (code "50") (name "unconnected-(U1A-BDBUS7-Pad24)") (class "Default")
      (node (ref "U1") (pin "24") (pinfunction "BDBUS7_24") (pintype "passive+no_connect"))
    )
    (net (code "51") (name "unconnected-(U1A-CDBUS4-Pad38)") (class "Default")
      (node (ref "U1") (pin "38") (pinfunction "CDBUS4_38") (pintype "passive+no_connect"))
    )
    (net (code "52") (name "unconnected-(U1A-CDBUS5-Pad40)") (class "Default")
      (node (ref "U1") (pin "40") (pinfunction "CDBUS5_40") (pintype "passive+no_connect"))
    )
    (net (code "53") (name "unconnected-(U1A-CDBUS6-Pad41)") (class "Default")
      (node (ref "U1") (pin "41") (pinfunction "CDBUS6_41") (pintype "passive+no_connect"))
    )
    (net (code "54") (name "unconnected-(U1A-CDBUS7-Pad42)") (class "Default")
      (node (ref "U1") (pin "42") (pinfunction "CDBUS7_42") (pintype "passive+no_connect"))
    )
    (net (code "55") (name "unconnected-(U1A-DDBUS4-Pad49)") (class "Default")
      (node (ref "U1") (pin "49") (pinfunction "DDBUS4_49") (pintype "passive+no_connect"))
    )
    (net (code "56") (name "unconnected-(U1A-DDBUS5-Pad50)") (class "Default")
      (node (ref "U1") (pin "50") (pinfunction "DDBUS5_50") (pintype "passive+no_connect"))
    )
    (net (code "57") (name "unconnected-(U1A-DDBUS6-Pad52)") (class "Default")
      (node (ref "U1") (pin "52") (pinfunction "DDBUS6_52") (pintype "passive+no_connect"))
    )
    (net (code "58") (name "unconnected-(U1A-DDBUS7-Pad53)") (class "Default")
      (node (ref "U1") (pin "53") (pinfunction "DDBUS7_53") (pintype "passive+no_connect"))
    )
    (net (code "59") (name "unconnected-(U1A-FSOURCE-Pad32)") (class "Default")
      (node (ref "U1") (pin "32") (pinfunction "FSOURCE_32") (pintype "passive+no_connect"))
    )
    (net (code "60") (name "unconnected-(U1A-GPIO0-Pad56)") (class "Default")
      (node (ref "U1") (pin "56") (pinfunction "GPIO0_56") (pintype "passive+no_connect"))
    )
    (net (code "61") (name "unconnected-(U1A-GPIO1-Pad55)") (class "Default")
      (node (ref "U1") (pin "55") (pinfunction "GPIO1_55") (pintype "passive+no_connect"))
    )
    (net (code "62") (name "unconnected-(U1A-GPIO2-Pad54)") (class "Default")
      (node (ref "U1") (pin "54") (pinfunction "GPIO2_54") (pintype "passive+no_connect"))
    )
    (net (code "63") (name "unconnected-(U1A-GPIO3-Pad5)") (class "Default")
      (node (ref "U1") (pin "5") (pinfunction "GPIO3_5") (pintype "passive+no_connect"))
    )
    (net (code "64") (name "unconnected-(U1A-VPP-Pad33)") (class "Default")
      (node (ref "U1") (pin "33") (pinfunction "VPP_33") (pintype "passive+no_connect"))
    )
    (net (code "65") (name "unconnected-(U2-NC-Pad7)") (class "Default")
      (node (ref "U2") (pin "7") (pinfunction "NC_7") (pintype "passive+no_connect"))
    )
  )
)
